# Top.net
KiCad netlist of a schematic drawn in Altium Designer
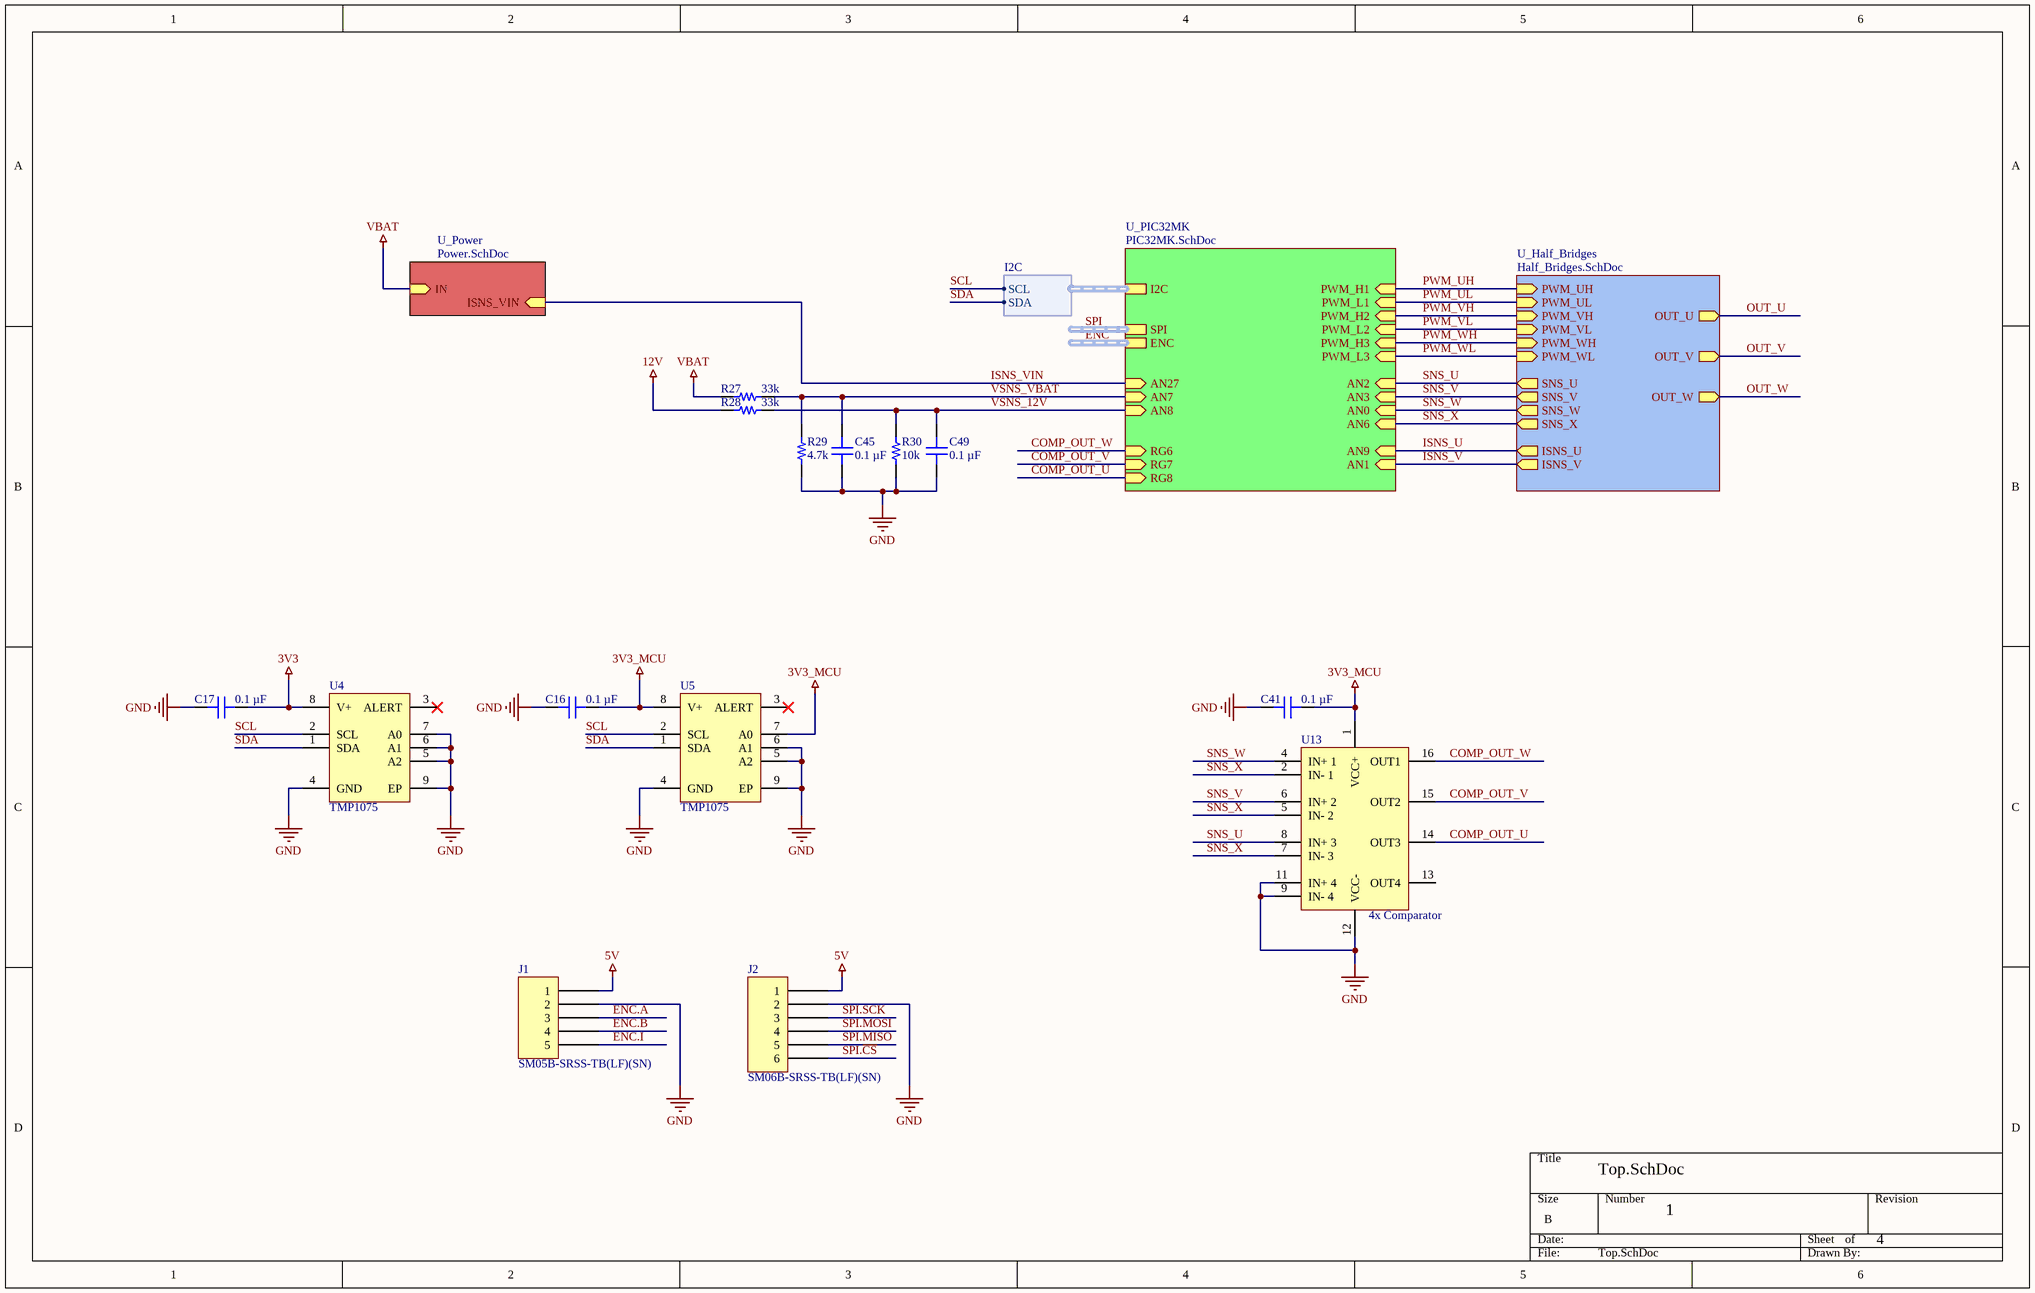
[diagram p0: Top.SchDoc]

(export (version "E")
  (design (tool "Eeschema 10.0.6"))
  (components
    (comp (ref "C16")
      (value "0.1 µF")
      (footprint "CAP 0402_1005")
      (description "CAP CER 0.1UF 16V X7R 0402")
      (fields (field (name "PART NUMBER") "C0402C104K4RACAUTO") (field (name "MANUFACTURER") "KEMET"))
      (libsource (lib "Celestial Altium Library - altium_library") (part "Capacitor"))
    )
    (comp (ref "C17")
      (value "0.1 µF")
      (footprint "CAP 0402_1005")
      (description "CAP CER 0.1UF 16V X7R 0402")
      (fields (field (name "PART NUMBER") "C0402C104K4RACAUTO") (field (name "MANUFACTURER") "KEMET"))
      (libsource (lib "Celestial Altium Library - altium_library") (part "Capacitor"))
    )
    (comp (ref "C41")
      (value "0.1 µF")
      (footprint "CAP 0402_1005")
      (description "CAP CER 0.1UF 16V X7R 0402")
      (fields (field (name "PART NUMBER") "C0402C104K4RACAUTO") (field (name "MANUFACTURER") "KEMET"))
      (libsource (lib "Celestial Altium Library - altium_library") (part "Capacitor"))
    )
    (comp (ref "C45")
      (value "0.1 µF")
      (footprint "CAP 0402_1005")
      (description "CAP CER 0.1UF 16V X7R 0402")
      (fields (field (name "PART NUMBER") "C0402C104K4RACAUTO") (field (name "MANUFACTURER") "KEMET"))
      (libsource (lib "Celestial Altium Library - altium_library") (part "Capacitor"))
    )
    (comp (ref "C49")
      (value "0.1 µF")
      (footprint "CAP 0402_1005")
      (description "CAP CER 0.1UF 16V X7R 0402")
      (fields (field (name "PART NUMBER") "C0402C104K4RACAUTO") (field (name "MANUFACTURER") "KEMET"))
      (libsource (lib "Celestial Altium Library - altium_library") (part "Capacitor"))
    )
    (comp (ref "J1")
      (value "SM05B-SRSS-TB(LF)(SN)")
      (footprint "JST SM05B-SRSS-TB")
      (description "CONN HEADER SMD R/A 5POS 1MM")
      (fields (field (name "MANUFACTURER") "JST Sales America Inc."))
      (libsource (lib "Celestial Altium Library - altium_library") (part "5 Pin"))
    )
    (comp (ref "J2")
      (value "SM06B-SRSS-TB(LF)(SN)")
      (footprint "JST SM06B-SRSS-TB")
      (description "CONN HEADER SMD R/A 6POS 1MM")
      (fields (field (name "MANUFACTURER") "JST Sales America Inc."))
      (libsource (lib "Celestial Altium Library - altium_library") (part "6 Pin"))
    )
    (comp (ref "R27")
      (value "33k")
      (footprint "RES 0402_1005")
      (description "RES 14.3K OHM 1% 1/10W 0402")
      (fields
        (field (name "PART NUMBER") "RK73H1ETTP1432F")
        (field (name "MANUFACTURER") "KOA Speer Electronics, Inc.")
      )
      (libsource (lib "Celestial Altium Library - altium_library") (part "Resistor"))
    )
    (comp (ref "R28")
      (value "33k")
      (footprint "RES 0402_1005")
      (description "RES 14.3K OHM 1% 1/10W 0402")
      (fields
        (field (name "PART NUMBER") "RK73H1ETTP1432F")
        (field (name "MANUFACTURER") "KOA Speer Electronics, Inc.")
      )
      (libsource (lib "Celestial Altium Library - altium_library") (part "Resistor"))
    )
    (comp (ref "R29")
      (value "4.7k")
      (footprint "RES 0402_1005")
      (description "RES 14.3K OHM 1% 1/10W 0402")
      (fields
        (field (name "PART NUMBER") "RK73H1ETTP1432F")
        (field (name "MANUFACTURER") "KOA Speer Electronics, Inc.")
      )
      (libsource (lib "Celestial Altium Library - altium_library") (part "Resistor"))
    )
    (comp (ref "R30")
      (value "10k")
      (footprint "RES 0402_1005")
      (description "RES 14.3K OHM 1% 1/10W 0402")
      (fields
        (field (name "PART NUMBER") "RK73H1ETTP1432F")
        (field (name "MANUFACTURER") "KOA Speer Electronics, Inc.")
      )
      (libsource (lib "Celestial Altium Library - altium_library") (part "Resistor"))
    )
    (comp (ref "U4")
      (value "TMP1075")
      (footprint "8_WSON_2x2_0.5mm")
      (description "I2C TEMP SENSOR")
      (libsource (lib "IC") (part "TMP1075"))
    )
    (comp (ref "U5")
      (value "TMP1075")
      (footprint "8_WSON_2x2_0.5mm")
      (description "I2C TEMP SENSOR")
      (libsource (lib "IC") (part "TMP1075"))
    )
    (comp (ref "U13")
      (value "4x Comparator")
      (footprint "QFN50P300X300X100-16N")
      (description "Comparator General Purpose CMOS, DTL, MOS, Open-Collector, TTL 16-QFN (3x3)")
      (libsource (lib "IC") (part "LM2901Q4T"))
    )
  )
  (nets
    (net (code "4") (name "/COMP_OUT_U") (class "Default")
      (node (ref "U13") (pin "14") (pinfunction "OUT3_14") (pintype "passive"))
    )
    (net (code "5") (name "/COMP_OUT_V") (class "Default")
      (node (ref "U13") (pin "15") (pinfunction "OUT2_15") (pintype "passive"))
    )
    (net (code "6") (name "/COMP_OUT_W") (class "Default")
      (node (ref "U13") (pin "16") (pinfunction "OUT1_16") (pintype "passive"))
    )
    (net (code "7") (name "/ENC.A") (class "Default")
      (node (ref "J1") (pin "3") (pinfunction "3_3") (pintype "passive"))
    )
    (net (code "8") (name "/ENC.B") (class "Default")
      (node (ref "J1") (pin "4") (pinfunction "4_4") (pintype "passive"))
    )
    (net (code "9") (name "/ENC.I") (class "Default")
      (node (ref "J1") (pin "5") (pinfunction "5_5") (pintype "passive"))
    )
    (net (code "22") (name "/SCL") (class "Default")
      (node (ref "U4") (pin "2") (pinfunction "SCL_2") (pintype "passive"))
      (node (ref "U5") (pin "2") (pinfunction "SCL_2") (pintype "passive"))
    )
    (net (code "23") (name "/SDA") (class "Default")
      (node (ref "U4") (pin "1") (pinfunction "SDA_1") (pintype "passive"))
      (node (ref "U5") (pin "1") (pinfunction "SDA_1") (pintype "passive"))
    )
    (net (code "24") (name "/SNS_U") (class "Default")
      (node (ref "U13") (pin "8") (pinfunction "IN+_3_8") (pintype "passive"))
    )
    (net (code "25") (name "/SNS_V") (class "Default")
      (node (ref "U13") (pin "6") (pinfunction "IN+_2_6") (pintype "passive"))
    )
    (net (code "26") (name "/SNS_W") (class "Default")
      (node (ref "U13") (pin "4") (pinfunction "IN+_1_4") (pintype "passive"))
    )
    (net (code "27") (name "/SNS_X") (class "Default")
      (node (ref "U13") (pin "2") (pinfunction "IN-_1_2") (pintype "passive"))
      (node (ref "U13") (pin "5") (pinfunction "IN-_2_5") (pintype "passive"))
      (node (ref "U13") (pin "7") (pinfunction "IN-_3_7") (pintype "passive"))
    )
    (net (code "28") (name "/SPI.MISO") (class "Default")
      (node (ref "J2") (pin "5") (pinfunction "5_5") (pintype "passive"))
    )
    (net (code "29") (name "/SPI.MOSI") (class "Default")
      (node (ref "J2") (pin "4") (pinfunction "4_4") (pintype "passive"))
    )
    (net (code "30") (name "/SPI.SCK") (class "Default")
      (node (ref "J2") (pin "3") (pinfunction "3_3") (pintype "passive"))
    )
    (net (code "31") (name "/SPI.~{CS}") (class "Default")
      (node (ref "J2") (pin "6") (pinfunction "6_6") (pintype "passive"))
    )
    (net (code "32") (name "/VSNS_12V") (class "Default")
      (node (ref "C49") (pin "2") (pinfunction "2_2") (pintype "passive"))
      (node (ref "R28") (pin "1") (pinfunction "1_1") (pintype "passive"))
      (node (ref "R30") (pin "1") (pinfunction "1_1") (pintype "passive"))
    )
    (net (code "33") (name "/VSNS_VBAT") (class "Default")
      (node (ref "C45") (pin "2") (pinfunction "2_2") (pintype "passive"))
      (node (ref "R27") (pin "1") (pinfunction "1_1") (pintype "passive"))
      (node (ref "R29") (pin "1") (pinfunction "1_1") (pintype "passive"))
    )
    (net (code "37") (name "3V3") (class "Default")
      (node (ref "C17") (pin "2") (pinfunction "2_2") (pintype "passive"))
      (node (ref "U4") (pin "8") (pinfunction "V+_8") (pintype "passive"))
    )
    (net (code "38") (name "3V3_MCU") (class "Default")
      (node (ref "C16") (pin "2") (pinfunction "2_2") (pintype "passive"))
      (node (ref "C41") (pin "2") (pinfunction "2_2") (pintype "passive"))
      (node (ref "U13") (pin "1") (pinfunction "VCC+_1") (pintype "passive"))
      (node (ref "U5") (pin "7") (pinfunction "A0_7") (pintype "passive"))
      (node (ref "U5") (pin "8") (pinfunction "V+_8") (pintype "passive"))
    )
    (net (code "39") (name "5V") (class "Default")
      (node (ref "J1") (pin "1") (pinfunction "1_1") (pintype "passive"))
      (node (ref "J2") (pin "1") (pinfunction "1_1") (pintype "passive"))
    )
    (net (code "40") (name "12V") (class "Default")
      (node (ref "R28") (pin "2") (pinfunction "2_2") (pintype "passive"))
    )
    (net (code "41") (name "GND") (class "Default")
      (node (ref "C16") (pin "1") (pinfunction "1_1") (pintype "passive"))
      (node (ref "C17") (pin "1") (pinfunction "1_1") (pintype "passive"))
      (node (ref "C41") (pin "1") (pinfunction "1_1") (pintype "passive"))
      (node (ref "C45") (pin "1") (pinfunction "1_1") (pintype "passive"))
      (node (ref "C49") (pin "1") (pinfunction "1_1") (pintype "passive"))
      (node (ref "J1") (pin "2") (pinfunction "2_2") (pintype "passive"))
      (node (ref "J2") (pin "2") (pinfunction "2_2") (pintype "passive"))
      (node (ref "R29") (pin "2") (pinfunction "2_2") (pintype "passive"))
      (node (ref "R30") (pin "2") (pinfunction "2_2") (pintype "passive"))
      (node (ref "U13") (pin "11") (pinfunction "IN+_4_11") (pintype "passive"))
      (node (ref "U13") (pin "12") (pinfunction "VCC-_12") (pintype "passive"))
      (node (ref "U13") (pin "9") (pinfunction "IN-_4_9") (pintype "passive"))
      (node (ref "U4") (pin "4") (pinfunction "GND_4") (pintype "passive"))
      (node (ref "U4") (pin "5") (pinfunction "A2_5") (pintype "passive"))
      (node (ref "U4") (pin "6") (pinfunction "A1_6") (pintype "passive"))
      (node (ref "U4") (pin "7") (pinfunction "A0_7") (pintype "passive"))
      (node (ref "U4") (pin "9") (pinfunction "EP_9") (pintype "passive"))
      (node (ref "U5") (pin "4") (pinfunction "GND_4") (pintype "passive"))
      (node (ref "U5") (pin "5") (pinfunction "A2_5") (pintype "passive"))
      (node (ref "U5") (pin "6") (pinfunction "A1_6") (pintype "passive"))
      (node (ref "U5") (pin "9") (pinfunction "EP_9") (pintype "passive"))
    )
    (net (code "42") (name "VBAT") (class "Default")
      (node (ref "R27") (pin "2") (pinfunction "2_2") (pintype "passive"))
    )
    (net (code "43") (name "unconnected-(U4-ALERT-Pad3)") (class "Default")
      (node (ref "U4") (pin "3") (pinfunction "ALERT_3") (pintype "passive+no_connect"))
    )
    (net (code "44") (name "unconnected-(U5-ALERT-Pad3)") (class "Default")
      (node (ref "U5") (pin "3") (pinfunction "ALERT_3") (pintype "passive+no_connect"))
    )
    (net (code "45") (name "unconnected-(U13-OUT4-Pad13)") (class "Default")
      (node (ref "U13") (pin "13") (pinfunction "OUT4_13") (pintype "passive"))
    )
  )
)
